# Altium_1_v01_Cartridge_Breakout.net
KiCad netlist of a schematic drawn in Altium Designer
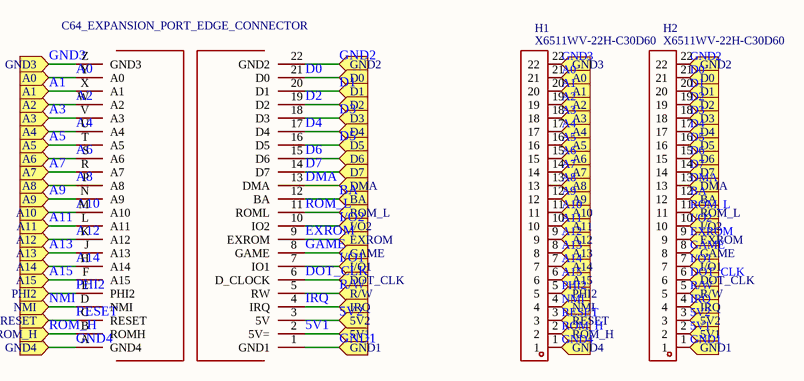
[diagram p0: Altium_1_v01_Cartridge_Breakout.schdoc]

(export (version "E")
  (design (tool "Eeschema 10.0.6"))
  (components
    (comp (ref "H1")
      (value "X6511WV-22H-C30D60")
      (footprint "HDR-TH_22P-P2.54-V-M")
      (fields
        (field (name "MANUFACTURER") "XKB Connection(中国星坤)")
        (field (name "MANUFACTURER PART") "X6511WV-22H-C60D30")
      )
      (libsource (lib "altium-import") (part "root_2_X6511WV-22H-C30D60_"))
    )
    (comp (ref "H2")
      (value "X6511WV-22H-C30D60")
      (footprint "HDR-TH_22P-P2.54-V-M")
      (fields
        (field (name "MANUFACTURER") "XKB Connection(中国星坤)")
        (field (name "MANUFACTURER PART") "X6511WV-22H-C60D30")
      )
      (libsource (lib "altium-import") (part "root_2_X6511WV-22H-C30D60_"))
    )
    (comp (ref "U1")
      (value "C64_EXPANSION_PORT_EDGE_CONNECTOR")
      (fields (field (name "MANUFACTURER PART") "?"))
      (libsource (lib "altium-import") (part "root_0_C64_EXPANSION_PORT_EDGE_CONNECTOR_"))
    )
  )
  (nets
    (net (code "1") (name "/5V1") (class "Default")
      (node (ref "H2") (pin "2") (pinfunction "2_2") (pintype "passive"))
      (node (ref "U1") (pin "2") (pinfunction "5V=_2") (pintype "passive"))
    )
    (net (code "2") (name "/5V2") (class "Default")
      (node (ref "H2") (pin "3") (pinfunction "3_3") (pintype "passive"))
      (node (ref "U1") (pin "3") (pinfunction "5V_3") (pintype "passive"))
    )
    (net (code "3") (name "/A0") (class "Default")
      (node (ref "H1") (pin "21") (pinfunction "21_21") (pintype "passive"))
      (node (ref "U1") (pin "Y") (pinfunction "A0_Y") (pintype "passive"))
    )
    (net (code "4") (name "/A1") (class "Default")
      (node (ref "H1") (pin "20") (pinfunction "20_20") (pintype "passive"))
      (node (ref "U1") (pin "X") (pinfunction "A1_X") (pintype "passive"))
    )
    (net (code "5") (name "/A2") (class "Default")
      (node (ref "H1") (pin "19") (pinfunction "19_19") (pintype "passive"))
      (node (ref "U1") (pin "W") (pinfunction "A2_W") (pintype "passive"))
    )
    (net (code "6") (name "/A3") (class "Default")
      (node (ref "H1") (pin "18") (pinfunction "18_18") (pintype "passive"))
      (node (ref "U1") (pin "V") (pinfunction "A3_V") (pintype "passive"))
    )
    (net (code "7") (name "/A4") (class "Default")
      (node (ref "H1") (pin "17") (pinfunction "17_17") (pintype "passive"))
      (node (ref "U1") (pin "U") (pinfunction "A4_U") (pintype "passive"))
    )
    (net (code "8") (name "/A5") (class "Default")
      (node (ref "H1") (pin "16") (pinfunction "16_16") (pintype "passive"))
      (node (ref "U1") (pin "T") (pinfunction "A5_T") (pintype "passive"))
    )
    (net (code "9") (name "/A6") (class "Default")
      (node (ref "H1") (pin "15") (pinfunction "15_15") (pintype "passive"))
      (node (ref "U1") (pin "S") (pinfunction "A6_S") (pintype "passive"))
    )
    (net (code "10") (name "/A7") (class "Default")
      (node (ref "H1") (pin "14") (pinfunction "14_14") (pintype "passive"))
      (node (ref "U1") (pin "R") (pinfunction "A7_R") (pintype "passive"))
    )
    (net (code "11") (name "/A8") (class "Default")
      (node (ref "H1") (pin "13") (pinfunction "13_13") (pintype "passive"))
      (node (ref "U1") (pin "P") (pinfunction "A8_P") (pintype "passive"))
    )
    (net (code "12") (name "/A9") (class "Default")
      (node (ref "H1") (pin "12") (pinfunction "12_12") (pintype "passive"))
      (node (ref "U1") (pin "N") (pinfunction "A9_N") (pintype "passive"))
    )
    (net (code "13") (name "/A10") (class "Default")
      (node (ref "H1") (pin "11") (pinfunction "11_11") (pintype "passive"))
      (node (ref "U1") (pin "M") (pinfunction "A10_M") (pintype "passive"))
    )
    (net (code "14") (name "/A11") (class "Default")
      (node (ref "H1") (pin "10") (pinfunction "10_10") (pintype "passive"))
      (node (ref "U1") (pin "L") (pinfunction "A11_L") (pintype "passive"))
    )
    (net (code "15") (name "/A12") (class "Default")
      (node (ref "H1") (pin "9") (pinfunction "9_9") (pintype "passive"))
      (node (ref "U1") (pin "K") (pinfunction "A12_K") (pintype "passive"))
    )
    (net (code "16") (name "/A13") (class "Default")
      (node (ref "H1") (pin "8") (pinfunction "8_8") (pintype "passive"))
      (node (ref "U1") (pin "J") (pinfunction "A13_J") (pintype "passive"))
    )
    (net (code "17") (name "/A14") (class "Default")
      (node (ref "H1") (pin "7") (pinfunction "7_7") (pintype "passive"))
      (node (ref "U1") (pin "H") (pinfunction "A14_H") (pintype "passive"))
    )
    (net (code "18") (name "/A15") (class "Default")
      (node (ref "H1") (pin "6") (pinfunction "6_6") (pintype "passive"))
      (node (ref "U1") (pin "F") (pinfunction "A15_F") (pintype "passive"))
    )
    (net (code "19") (name "/BA") (class "Default")
      (node (ref "H2") (pin "12") (pinfunction "12_12") (pintype "passive"))
      (node (ref "U1") (pin "12") (pinfunction "BA_12") (pintype "passive"))
    )
    (net (code "20") (name "/D0") (class "Default")
      (node (ref "H2") (pin "21") (pinfunction "21_21") (pintype "passive"))
      (node (ref "U1") (pin "21") (pinfunction "D0_21") (pintype "passive"))
    )
    (net (code "21") (name "/D1") (class "Default")
      (node (ref "H2") (pin "20") (pinfunction "20_20") (pintype "passive"))
      (node (ref "U1") (pin "20") (pinfunction "D1_20") (pintype "passive"))
    )
    (net (code "22") (name "/D2") (class "Default")
      (node (ref "H2") (pin "19") (pinfunction "19_19") (pintype "passive"))
      (node (ref "U1") (pin "19") (pinfunction "D2_19") (pintype "passive"))
    )
    (net (code "23") (name "/D3") (class "Default")
      (node (ref "H2") (pin "18") (pinfunction "18_18") (pintype "passive"))
      (node (ref "U1") (pin "18") (pinfunction "D3_18") (pintype "passive"))
    )
    (net (code "24") (name "/D4") (class "Default")
      (node (ref "H2") (pin "17") (pinfunction "17_17") (pintype "passive"))
      (node (ref "U1") (pin "17") (pinfunction "D4_17") (pintype "passive"))
    )
    (net (code "25") (name "/D5") (class "Default")
      (node (ref "H2") (pin "16") (pinfunction "16_16") (pintype "passive"))
      (node (ref "U1") (pin "16") (pinfunction "D5_16") (pintype "passive"))
    )
    (net (code "26") (name "/D6") (class "Default")
      (node (ref "H2") (pin "15") (pinfunction "15_15") (pintype "passive"))
      (node (ref "U1") (pin "15") (pinfunction "D6_15") (pintype "passive"))
    )
    (net (code "27") (name "/D7") (class "Default")
      (node (ref "H2") (pin "14") (pinfunction "14_14") (pintype "passive"))
      (node (ref "U1") (pin "14") (pinfunction "D7_14") (pintype "passive"))
    )
    (net (code "28") (name "/DMA") (class "Default")
      (node (ref "H2") (pin "13") (pinfunction "13_13") (pintype "passive"))
      (node (ref "U1") (pin "13") (pinfunction "DMA_13") (pintype "passive"))
    )
    (net (code "29") (name "/DOT_CLK") (class "Default")
      (node (ref "H2") (pin "6") (pinfunction "6_6") (pintype "passive"))
      (node (ref "U1") (pin "6") (pinfunction "D_CLOCK_6") (pintype "passive"))
    )
    (net (code "30") (name "/EXROM") (class "Default")
      (node (ref "H2") (pin "9") (pinfunction "9_9") (pintype "passive"))
      (node (ref "U1") (pin "9") (pinfunction "EXROM_9") (pintype "passive"))
    )
    (net (code "31") (name "/GAME") (class "Default")
      (node (ref "H2") (pin "8") (pinfunction "8_8") (pintype "passive"))
      (node (ref "U1") (pin "8") (pinfunction "GAME_8") (pintype "passive"))
    )
    (net (code "32") (name "/GND1") (class "Default")
      (node (ref "H2") (pin "1") (pinfunction "1_1") (pintype "passive"))
      (node (ref "U1") (pin "1") (pinfunction "GND1_1") (pintype "passive"))
    )
    (net (code "33") (name "/GND2") (class "Default")
      (node (ref "H2") (pin "22") (pinfunction "22_22") (pintype "passive"))
      (node (ref "U1") (pin "22") (pinfunction "GND2_22") (pintype "passive"))
    )
    (net (code "34") (name "/GND3") (class "Default")
      (node (ref "H1") (pin "22") (pinfunction "22_22") (pintype "passive"))
      (node (ref "U1") (pin "Z") (pinfunction "GND3_Z") (pintype "passive"))
    )
    (net (code "35") (name "/GND4") (class "Default")
      (node (ref "H1") (pin "1") (pinfunction "1_1") (pintype "passive"))
      (node (ref "U1") (pin "A") (pinfunction "GND4_A") (pintype "passive"))
    )
    (net (code "36") (name "/IRQ") (class "Default")
      (node (ref "H2") (pin "4") (pinfunction "4_4") (pintype "passive"))
      (node (ref "U1") (pin "4") (pinfunction "IRQ_4") (pintype "passive"))
    )
    (net (code "37") (name "/I{slash}O1") (class "Default")
      (node (ref "H2") (pin "7") (pinfunction "7_7") (pintype "passive"))
      (node (ref "U1") (pin "7") (pinfunction "IO1_7") (pintype "passive"))
    )
    (net (code "38") (name "/I{slash}O2") (class "Default")
      (node (ref "H2") (pin "10") (pinfunction "10_10") (pintype "passive"))
      (node (ref "U1") (pin "10") (pinfunction "IO2_10") (pintype "passive"))
    )
    (net (code "39") (name "/NMI") (class "Default")
      (node (ref "H1") (pin "4") (pinfunction "4_4") (pintype "passive"))
      (node (ref "U1") (pin "D") (pinfunction "NMI_D") (pintype "passive"))
    )
    (net (code "40") (name "/PHI2") (class "Default")
      (node (ref "H1") (pin "5") (pinfunction "5_5") (pintype "passive"))
      (node (ref "U1") (pin "E") (pinfunction "PHI2_E") (pintype "passive"))
    )
    (net (code "41") (name "/RESET") (class "Default")
      (node (ref "H1") (pin "3") (pinfunction "3_3") (pintype "passive"))
      (node (ref "U1") (pin "C") (pinfunction "RESET_C") (pintype "passive"))
    )
    (net (code "42") (name "/ROM_H") (class "Default")
      (node (ref "H1") (pin "2") (pinfunction "2_2") (pintype "passive"))
      (node (ref "U1") (pin "B") (pinfunction "ROMH_B") (pintype "passive"))
    )
    (net (code "43") (name "/ROM_L") (class "Default")
      (node (ref "H2") (pin "11") (pinfunction "11_11") (pintype "passive"))
      (node (ref "U1") (pin "11") (pinfunction "ROML_11") (pintype "passive"))
    )
    (net (code "44") (name "/R{slash}W") (class "Default")
      (node (ref "H2") (pin "5") (pinfunction "5_5") (pintype "passive"))
      (node (ref "U1") (pin "5") (pinfunction "RW_5") (pintype "passive"))
    )
  )
)
